# HB_UNIT.net
KiCad netlist of a schematic drawn in Altium Designer
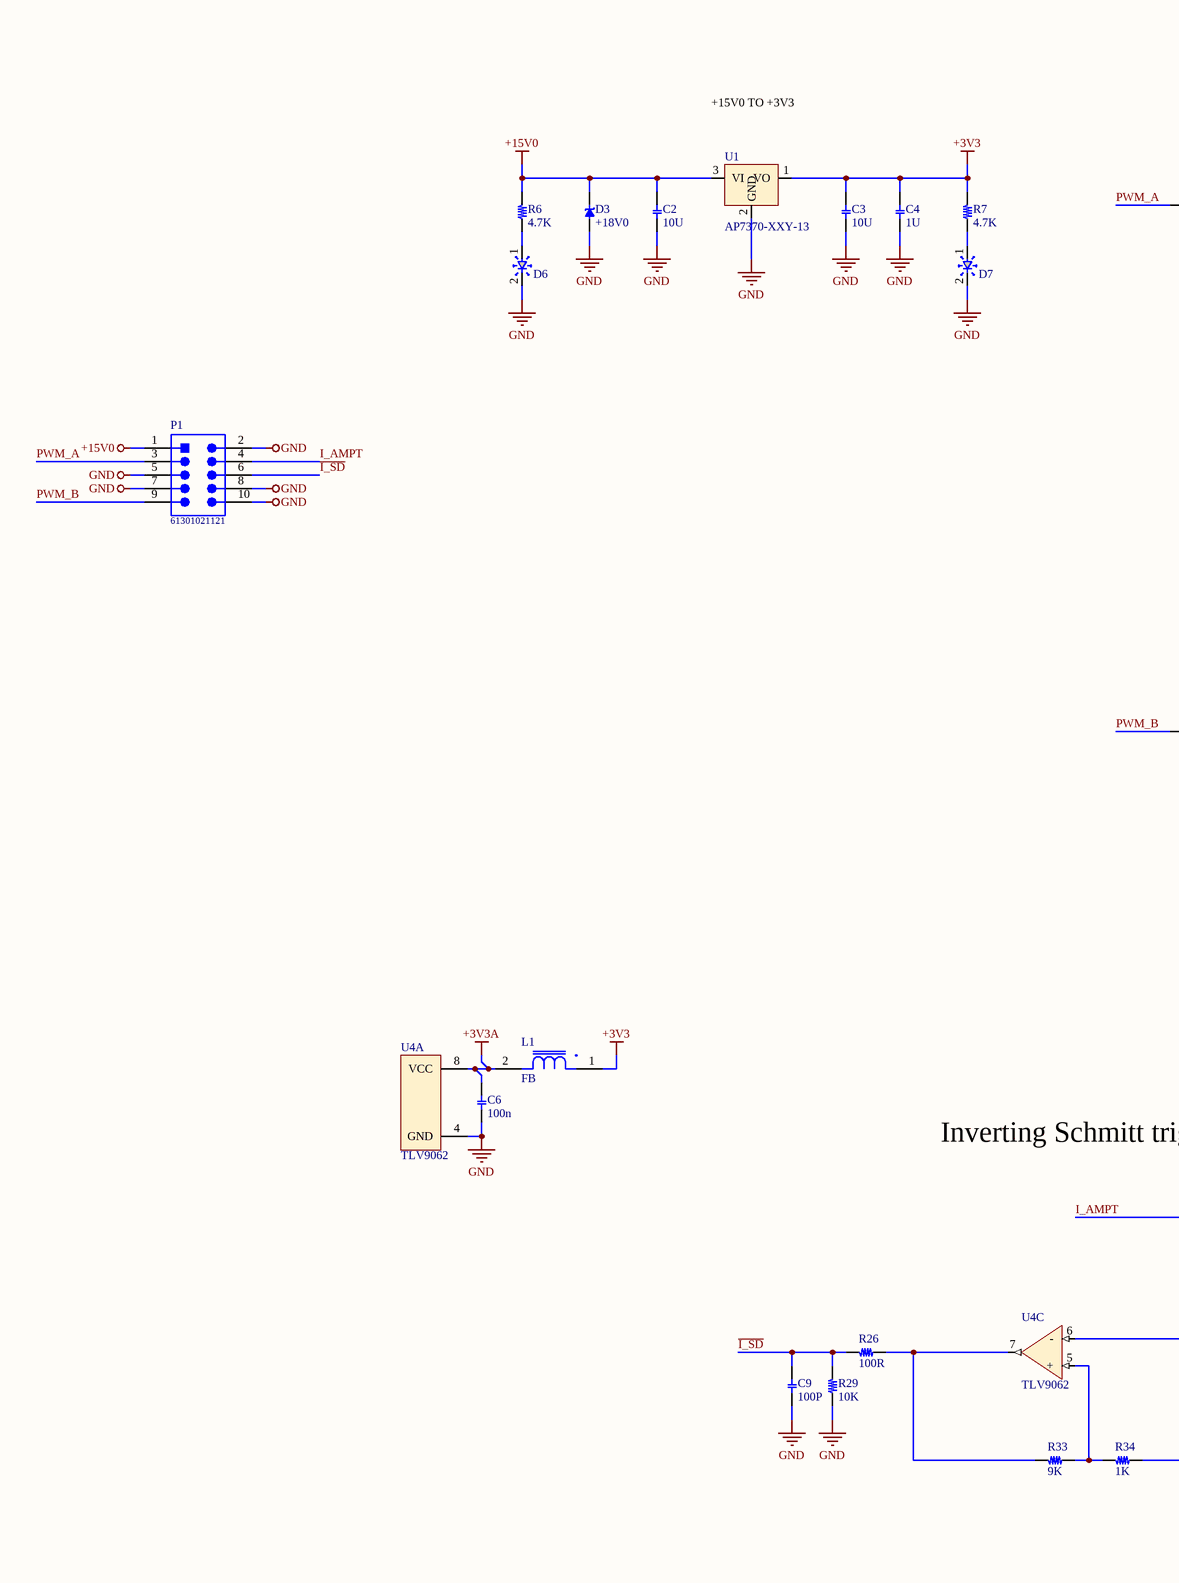
[diagram p0: HB_UNIT.SchDoc, left]
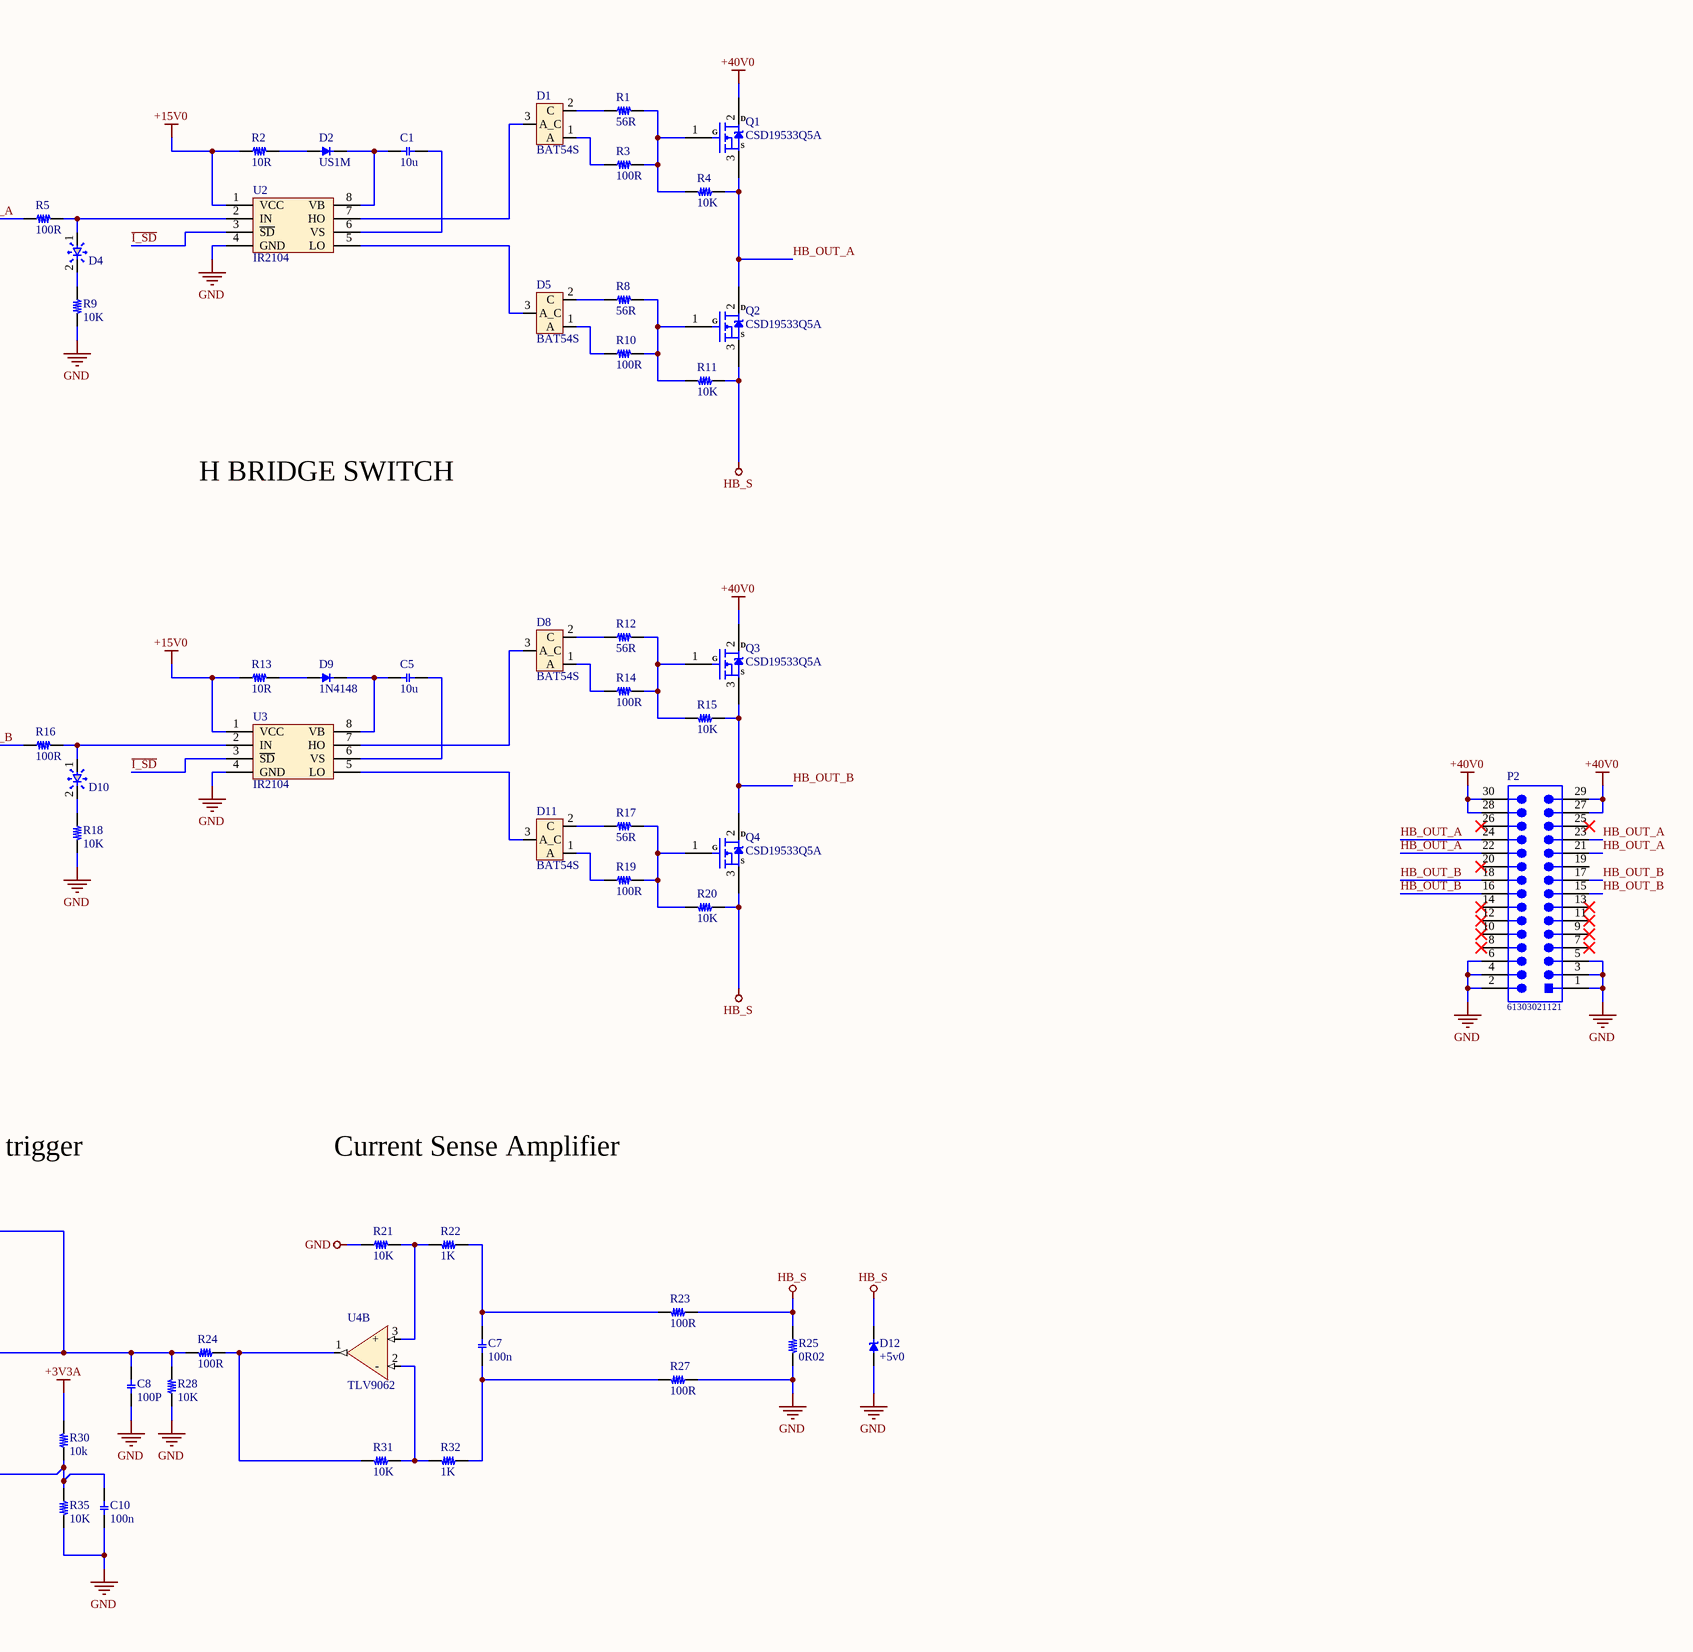
[diagram p1: HB_UNIT.SchDoc, right]

(export (version "E")
  (design (tool "Eeschema 10.0.6"))
  (components
    (comp (ref "C1")
      (value "10u")
      (footprint "C 0805")
      (description "CAP_SMD")
      (libsource (lib "radmehr_library") (part "CAP_SMD"))
    )
    (comp (ref "C2")
      (value "10U")
      (footprint "C 0603")
      (description "CAP_SMD")
      (libsource (lib "radmehr_library") (part "CAP_SMD"))
    )
    (comp (ref "C3")
      (value "10U")
      (footprint "C 0603")
      (description "CAP_SMD")
      (libsource (lib "radmehr_library") (part "CAP_SMD"))
    )
    (comp (ref "C4")
      (value "1U")
      (footprint "C 0603")
      (description "CAP_SMD")
      (libsource (lib "radmehr_library") (part "CAP_SMD"))
    )
    (comp (ref "C5")
      (value "10u")
      (footprint "C 0805")
      (description "CAP_SMD")
      (libsource (lib "radmehr_library") (part "CAP_SMD"))
    )
    (comp (ref "C6")
      (value "100n")
      (footprint "C 0603")
      (description "CAP_SMD")
      (libsource (lib "radmehr_library") (part "CAP_SMD"))
    )
    (comp (ref "C7")
      (value "100n")
      (footprint "C 0603")
      (description "CAP_SMD")
      (libsource (lib "radmehr_library") (part "CAP_SMD"))
    )
    (comp (ref "C8")
      (value "100P")
      (footprint "C 0603")
      (description "CAP_SMD")
      (libsource (lib "radmehr_library") (part "CAP_SMD"))
    )
    (comp (ref "C9")
      (value "100P")
      (footprint "C 0603")
      (description "CAP_SMD")
      (libsource (lib "radmehr_library") (part "CAP_SMD"))
    )
    (comp (ref "C10")
      (value "100n")
      (footprint "C 0603")
      (description "CAP_SMD")
      (libsource (lib "radmehr_library") (part "CAP_SMD"))
    )
    (comp (ref "D1")
      (value "BAT54S")
      (footprint "SOT-23_3_D")
      (libsource (lib "radmehr_library") (part "BAT54S"))
    )
    (comp (ref "D2")
      (value "US1M")
      (footprint "D SOD-123")
      (description "DIOD_SMD")
      (libsource (lib "radmehr_library") (part "DIOD_SMD"))
    )
    (comp (ref "D3")
      (value "+18V0")
      (footprint "DIOD_SMB")
      (description "TVS_UI")
      (libsource (lib "radmehr_library") (part "DIOD_SMD_TVS_UI"))
    )
    (comp (ref "D4")
      (value "LED_SMD")
      (footprint "D 0603")
      (libsource (lib "radmehr_library") (part "LED_SMD"))
    )
    (comp (ref "D5")
      (value "BAT54S")
      (footprint "SOT-23_3_D")
      (libsource (lib "radmehr_library") (part "BAT54S"))
    )
    (comp (ref "D6")
      (value "LED_SMD")
      (footprint "D 0603")
      (libsource (lib "radmehr_library") (part "LED_SMD"))
    )
    (comp (ref "D7")
      (value "LED_SMD")
      (footprint "D 0603")
      (libsource (lib "radmehr_library") (part "LED_SMD"))
    )
    (comp (ref "D8")
      (value "BAT54S")
      (footprint "SOT-23_3_D")
      (libsource (lib "radmehr_library") (part "BAT54S"))
    )
    (comp (ref "D9")
      (value "1N4148")
      (footprint "D SOD-123")
      (description "DIOD_SMD")
      (libsource (lib "radmehr_library") (part "DIOD_SMD"))
    )
    (comp (ref "D10")
      (value "LED_SMD")
      (footprint "D 0603")
      (libsource (lib "radmehr_library") (part "LED_SMD"))
    )
    (comp (ref "D11")
      (value "BAT54S")
      (footprint "SOT-23_3_D")
      (libsource (lib "radmehr_library") (part "BAT54S"))
    )
    (comp (ref "D12")
      (value "+5v0")
      (footprint "DIOD_SMB")
      (description "TVS_UI")
      (libsource (lib "radmehr_library") (part "DIOD_SMD_TVS_UI"))
    )
    (comp (ref "L1")
      (value "FB")
      (footprint "L 0603")
      (description "Inductor")
      (libsource (lib "radmehr_library") (part "Inductor"))
    )
    (comp (ref "P1")
      (value "61301021121")
      (footprint "61301021121")
      (description "WR-PHD Pin Header, THT, pitch 2.54mm, Dual Row, Vertical, 10p")
      (fields (field (name "MANUFACTURER") "Wurth Elektronik"))
      (libsource (lib "Altium_WR-PHD (rev22a)") (part "61301021121"))
    )
    (comp (ref "P2")
      (value "61303021121")
      (footprint "61303021121")
      (description "WR-PHD Pin Header, THT, pitch 2.54mm, Dual Row, Vertical, 30p")
      (fields (field (name "MANUFACTURER") "Wurth Elektronik"))
      (libsource (lib "Altium_WR-PHD (rev22a)") (part "61303021121"))
    )
    (comp (ref "Q1")
      (value "CSD19533Q5A")
      (footprint "Q5A")
      (libsource (lib "radmehr_library") (part "CSD19533Q5A"))
    )
    (comp (ref "Q2")
      (value "CSD19533Q5A")
      (footprint "Q5A")
      (libsource (lib "radmehr_library") (part "CSD19533Q5A"))
    )
    (comp (ref "Q3")
      (value "CSD19533Q5A")
      (footprint "Q5A")
      (libsource (lib "radmehr_library") (part "CSD19533Q5A"))
    )
    (comp (ref "Q4")
      (value "CSD19533Q5A")
      (footprint "Q5A")
      (libsource (lib "radmehr_library") (part "CSD19533Q5A"))
    )
    (comp (ref "R1")
      (value "56R")
      (footprint "R 0805")
      (description "RES_SMD")
      (libsource (lib "radmehr_library") (part "RES_SMD"))
    )
    (comp (ref "R2")
      (value "10R")
      (footprint "R 0805")
      (description "RES_SMD")
      (libsource (lib "radmehr_library") (part "RES_SMD"))
    )
    (comp (ref "R3")
      (value "100R")
      (footprint "R 0805")
      (description "RES_SMD")
      (libsource (lib "radmehr_library") (part "RES_SMD"))
    )
    (comp (ref "R4")
      (value "10K")
      (footprint "R 0603")
      (description "RES_SMD")
      (libsource (lib "radmehr_library") (part "RES_SMD"))
    )
    (comp (ref "R5")
      (value "100R")
      (footprint "R 0603")
      (description "RES_SMD")
      (libsource (lib "radmehr_library") (part "RES_SMD"))
    )
    (comp (ref "R6")
      (value "4.7K")
      (footprint "R 0603")
      (description "RES_SMD")
      (libsource (lib "radmehr_library") (part "RES_SMD"))
    )
    (comp (ref "R7")
      (value "4.7K")
      (footprint "R 0603")
      (description "RES_SMD")
      (libsource (lib "radmehr_library") (part "RES_SMD"))
    )
    (comp (ref "R8")
      (value "56R")
      (footprint "R 0805")
      (description "RES_SMD")
      (libsource (lib "radmehr_library") (part "RES_SMD"))
    )
    (comp (ref "R9")
      (value "10K")
      (footprint "R 0603")
      (description "RES_SMD")
      (libsource (lib "radmehr_library") (part "RES_SMD"))
    )
    (comp (ref "R10")
      (value "100R")
      (footprint "R 0805")
      (description "RES_SMD")
      (libsource (lib "radmehr_library") (part "RES_SMD"))
    )
    (comp (ref "R11")
      (value "10K")
      (footprint "R 0603")
      (description "RES_SMD")
      (libsource (lib "radmehr_library") (part "RES_SMD"))
    )
    (comp (ref "R12")
      (value "56R")
      (footprint "R 0805")
      (description "RES_SMD")
      (libsource (lib "radmehr_library") (part "RES_SMD"))
    )
    (comp (ref "R13")
      (value "10R")
      (footprint "R 0805")
      (description "RES_SMD")
      (libsource (lib "radmehr_library") (part "RES_SMD"))
    )
    (comp (ref "R14")
      (value "100R")
      (footprint "R 0805")
      (description "RES_SMD")
      (libsource (lib "radmehr_library") (part "RES_SMD"))
    )
    (comp (ref "R15")
      (value "10K")
      (footprint "R 0603")
      (description "RES_SMD")
      (libsource (lib "radmehr_library") (part "RES_SMD"))
    )
    (comp (ref "R16")
      (value "100R")
      (footprint "R 0603")
      (description "RES_SMD")
      (libsource (lib "radmehr_library") (part "RES_SMD"))
    )
    (comp (ref "R17")
      (value "56R")
      (footprint "R 0805")
      (description "RES_SMD")
      (libsource (lib "radmehr_library") (part "RES_SMD"))
    )
    (comp (ref "R18")
      (value "10K")
      (footprint "R 0603")
      (description "RES_SMD")
      (libsource (lib "radmehr_library") (part "RES_SMD"))
    )
    (comp (ref "R19")
      (value "100R")
      (footprint "R 0805")
      (description "RES_SMD")
      (libsource (lib "radmehr_library") (part "RES_SMD"))
    )
    (comp (ref "R20")
      (value "10K")
      (footprint "R 0603")
      (description "RES_SMD")
      (libsource (lib "radmehr_library") (part "RES_SMD"))
    )
    (comp (ref "R21")
      (value "10K")
      (footprint "R 0603")
      (description "RES_SMD")
      (libsource (lib "radmehr_library") (part "RES_SMD"))
    )
    (comp (ref "R22")
      (value "1K")
      (footprint "R 0603")
      (description "RES_SMD")
      (libsource (lib "radmehr_library") (part "RES_SMD"))
    )
    (comp (ref "R23")
      (value "100R")
      (footprint "R 0603")
      (description "RES_SMD")
      (libsource (lib "radmehr_library") (part "RES_SMD"))
    )
    (comp (ref "R24")
      (value "100R")
      (footprint "R 0603")
      (description "RES_SMD")
      (libsource (lib "radmehr_library") (part "RES_SMD"))
    )
    (comp (ref "R25")
      (value "0R02")
      (footprint "R 2512")
      (description "RES_SMD")
      (libsource (lib "radmehr_library") (part "RES_SMD"))
    )
    (comp (ref "R26")
      (value "100R")
      (footprint "R 0603")
      (description "RES_SMD")
      (libsource (lib "radmehr_library") (part "RES_SMD"))
    )
    (comp (ref "R27")
      (value "100R")
      (footprint "R 0603")
      (description "RES_SMD")
      (libsource (lib "radmehr_library") (part "RES_SMD"))
    )
    (comp (ref "R28")
      (value "10K")
      (footprint "R 0603")
      (description "RES_SMD")
      (libsource (lib "radmehr_library") (part "RES_SMD"))
    )
    (comp (ref "R29")
      (value "10K")
      (footprint "R 0603")
      (description "RES_SMD")
      (libsource (lib "radmehr_library") (part "RES_SMD"))
    )
    (comp (ref "R30")
      (value "10k")
      (footprint "R 0603")
      (description "RES_SMD")
      (libsource (lib "radmehr_library") (part "RES_SMD"))
    )
    (comp (ref "R31")
      (value "10K")
      (footprint "R 0603")
      (description "RES_SMD")
      (libsource (lib "radmehr_library") (part "RES_SMD"))
    )
    (comp (ref "R32")
      (value "1K")
      (footprint "R 0603")
      (description "RES_SMD")
      (libsource (lib "radmehr_library") (part "RES_SMD"))
    )
    (comp (ref "R33")
      (value "9K")
      (footprint "R 0603")
      (description "RES_SMD")
      (libsource (lib "radmehr_library") (part "RES_SMD"))
    )
    (comp (ref "R34")
      (value "1K")
      (footprint "R 0603")
      (description "RES_SMD")
      (libsource (lib "radmehr_library") (part "RES_SMD"))
    )
    (comp (ref "R35")
      (value "10K")
      (footprint "R 0603")
      (description "RES_SMD")
      (libsource (lib "radmehr_library") (part "RES_SMD"))
    )
    (comp (ref "U1")
      (value "AP7370-XXY-13")
      (footprint "SOT89-U")
      (libsource (lib "radmehr_library") (part "AP7370-XXY-13"))
    )
    (comp (ref "U2")
      (value "IR2104")
      (footprint "SOIC-8")
      (libsource (lib "radmehr_library") (part "IR2104"))
    )
    (comp (ref "U3")
      (value "IR2104")
      (footprint "SOIC-8")
      (libsource (lib "radmehr_library") (part "IR2104"))
    )
    (comp (ref "U4")
      (value "TLV9062")
      (footprint "SOIC-8")
      (libsource (lib "radmehr_library") (part "TLV9062"))
    )
  )
  (nets
    (net (code "1") (name "+3V3") (class "Default")
      (node (ref "C3") (pin "2") (pinfunction "2_2") (pintype "passive"))
      (node (ref "C4") (pin "2") (pinfunction "2_2") (pintype "passive"))
      (node (ref "L1") (pin "1") (pintype "passive"))
      (node (ref "R7") (pin "2") (pinfunction "2_2") (pintype "passive"))
      (node (ref "U1") (pin "1") (pinfunction "VO_1") (pintype "passive"))
    )
    (net (code "2") (name "+3V3A") (class "Default")
      (node (ref "C6") (pin "2") (pinfunction "2_2") (pintype "passive"))
      (node (ref "L1") (pin "2") (pintype "passive"))
      (node (ref "R30") (pin "1") (pinfunction "1_1") (pintype "passive"))
      (node (ref "U4") (pin "8") (pinfunction "VCC_8") (pintype "passive"))
    )
    (net (code "3") (name "+15V0") (class "Default")
      (node (ref "C2") (pin "2") (pinfunction "2_2") (pintype "passive"))
      (node (ref "D3") (pin "2") (pinfunction "2_2") (pintype "passive"))
      (node (ref "P1") (pin "1") (pinfunction "1_1") (pintype "passive"))
      (node (ref "R13") (pin "1") (pinfunction "1_1") (pintype "passive"))
      (node (ref "R2") (pin "1") (pinfunction "1_1") (pintype "passive"))
      (node (ref "R6") (pin "2") (pinfunction "2_2") (pintype "passive"))
      (node (ref "U1") (pin "3") (pinfunction "VI_3") (pintype "passive"))
      (node (ref "U2") (pin "1") (pinfunction "VCC_1") (pintype "passive"))
      (node (ref "U3") (pin "1") (pinfunction "VCC_1") (pintype "passive"))
    )
    (net (code "4") (name "+40V0") (class "Default")
      (node (ref "P2") (pin "27") (pinfunction "27_27") (pintype "passive"))
      (node (ref "P2") (pin "28") (pinfunction "28_28") (pintype "passive"))
      (node (ref "P2") (pin "29") (pinfunction "29_29") (pintype "passive"))
      (node (ref "P2") (pin "30") (pinfunction "30_30") (pintype "passive"))
      (node (ref "Q1") (pin "2") (pinfunction "D_2") (pintype "passive"))
      (node (ref "Q3") (pin "2") (pinfunction "D_2") (pintype "passive"))
    )
    (net (code "5") (name "/HB_OUT_A") (class "Default")
      (node (ref "P2") (pin "21") (pinfunction "21_21") (pintype "passive"))
      (node (ref "P2") (pin "22") (pinfunction "22_22") (pintype "passive"))
      (node (ref "P2") (pin "23") (pinfunction "23_23") (pintype "passive"))
      (node (ref "P2") (pin "24") (pinfunction "24_24") (pintype "passive"))
      (node (ref "Q1") (pin "3") (pinfunction "S_3") (pintype "passive"))
      (node (ref "Q2") (pin "2") (pinfunction "D_2") (pintype "passive"))
      (node (ref "R4") (pin "1") (pinfunction "1_1") (pintype "passive"))
    )
    (net (code "6") (name "/HB_OUT_B") (class "Default")
      (node (ref "P2") (pin "15") (pinfunction "15_15") (pintype "passive"))
      (node (ref "P2") (pin "16") (pinfunction "16_16") (pintype "passive"))
      (node (ref "P2") (pin "17") (pinfunction "17_17") (pintype "passive"))
      (node (ref "P2") (pin "18") (pinfunction "18_18") (pintype "passive"))
      (node (ref "Q3") (pin "3") (pinfunction "S_3") (pintype "passive"))
      (node (ref "Q4") (pin "2") (pinfunction "D_2") (pintype "passive"))
      (node (ref "R15") (pin "1") (pinfunction "1_1") (pintype "passive"))
    )
    (net (code "7") (name "/I_AMPT") (class "Default")
      (node (ref "C8") (pin "2") (pinfunction "2_2") (pintype "passive"))
      (node (ref "P1") (pin "4") (pinfunction "4_4") (pintype "passive"))
      (node (ref "R24") (pin "2") (pinfunction "2_2") (pintype "passive"))
      (node (ref "R28") (pin "2") (pinfunction "2_2") (pintype "passive"))
      (node (ref "U4") (pin "6") (pinfunction "-_6") (pintype "input"))
    )
    (net (code "8") (name "/PWM_A") (class "Default")
      (node (ref "P1") (pin "3") (pinfunction "3_3") (pintype "passive"))
      (node (ref "R5") (pin "1") (pinfunction "1_1") (pintype "passive"))
    )
    (net (code "9") (name "/PWM_B") (class "Default")
      (node (ref "P1") (pin "9") (pinfunction "9_9") (pintype "passive"))
      (node (ref "R16") (pin "1") (pinfunction "1_1") (pintype "passive"))
    )
    (net (code "10") (name "/~{I_SD}") (class "Default")
      (node (ref "C9") (pin "2") (pinfunction "2_2") (pintype "passive"))
      (node (ref "P1") (pin "6") (pinfunction "6_6") (pintype "passive"))
      (node (ref "R26") (pin "2") (pinfunction "2_2") (pintype "passive"))
      (node (ref "R29") (pin "2") (pinfunction "2_2") (pintype "passive"))
      (node (ref "U2") (pin "3") (pinfunction "~{SD}_3") (pintype "passive"))
      (node (ref "U3") (pin "3") (pinfunction "~{SD}_3") (pintype "passive"))
    )
    (net (code "11") (name "GND") (class "Default")
      (node (ref "C10") (pin "2") (pinfunction "2_2") (pintype "passive"))
      (node (ref "C2") (pin "1") (pinfunction "1_1") (pintype "passive"))
      (node (ref "C3") (pin "1") (pinfunction "1_1") (pintype "passive"))
      (node (ref "C4") (pin "1") (pinfunction "1_1") (pintype "passive"))
      (node (ref "C6") (pin "1") (pinfunction "1_1") (pintype "passive"))
      (node (ref "C8") (pin "1") (pinfunction "1_1") (pintype "passive"))
      (node (ref "C9") (pin "1") (pinfunction "1_1") (pintype "passive"))
      (node (ref "D12") (pin "1") (pinfunction "1_1") (pintype "passive"))
      (node (ref "D3") (pin "1") (pinfunction "1_1") (pintype "passive"))
      (node (ref "D6") (pin "2") (pintype "passive"))
      (node (ref "D7") (pin "2") (pintype "passive"))
      (node (ref "P1") (pin "10") (pinfunction "10_10") (pintype "passive"))
      (node (ref "P1") (pin "2") (pinfunction "2_2") (pintype "passive"))
      (node (ref "P1") (pin "5") (pinfunction "5_5") (pintype "passive"))
      (node (ref "P1") (pin "7") (pinfunction "7_7") (pintype "passive"))
      (node (ref "P1") (pin "8") (pinfunction "8_8") (pintype "passive"))
      (node (ref "P2") (pin "1") (pinfunction "1_1") (pintype "passive"))
      (node (ref "P2") (pin "2") (pinfunction "2_2") (pintype "passive"))
      (node (ref "P2") (pin "3") (pinfunction "3_3") (pintype "passive"))
      (node (ref "P2") (pin "4") (pinfunction "4_4") (pintype "passive"))
      (node (ref "P2") (pin "5") (pinfunction "5_5") (pintype "passive"))
      (node (ref "P2") (pin "6") (pinfunction "6_6") (pintype "passive"))
      (node (ref "R18") (pin "1") (pinfunction "1_1") (pintype "passive"))
      (node (ref "R21") (pin "1") (pinfunction "1_1") (pintype "passive"))
      (node (ref "R25") (pin "1") (pinfunction "1_1") (pintype "passive"))
      (node (ref "R27") (pin "1") (pinfunction "1_1") (pintype "passive"))
      (node (ref "R28") (pin "1") (pinfunction "1_1") (pintype "passive"))
      (node (ref "R29") (pin "1") (pinfunction "1_1") (pintype "passive"))
      (node (ref "R35") (pin "1") (pinfunction "1_1") (pintype "passive"))
      (node (ref "R9") (pin "1") (pinfunction "1_1") (pintype "passive"))
      (node (ref "U1") (pin "2") (pinfunction "GND_2") (pintype "passive"))
      (node (ref "U2") (pin "4") (pinfunction "GND_4") (pintype "passive"))
      (node (ref "U3") (pin "4") (pinfunction "GND_4") (pintype "passive"))
      (node (ref "U4") (pin "4") (pinfunction "GND_4") (pintype "passive"))
    )
    (net (code "12") (name "HB_S") (class "Default")
      (node (ref "D12") (pin "2") (pinfunction "2_2") (pintype "passive"))
      (node (ref "Q2") (pin "3") (pinfunction "S_3") (pintype "passive"))
      (node (ref "Q4") (pin "3") (pinfunction "S_3") (pintype "passive"))
      (node (ref "R11") (pin "1") (pinfunction "1_1") (pintype "passive"))
      (node (ref "R20") (pin "1") (pinfunction "1_1") (pintype "passive"))
      (node (ref "R23") (pin "1") (pinfunction "1_1") (pintype "passive"))
      (node (ref "R25") (pin "2") (pinfunction "2_2") (pintype "passive"))
    )
    (net (code "13") (name "Net-(C7-Pad1)") (class "Default")
      (node (ref "C7") (pin "1") (pinfunction "1_1") (pintype "passive"))
      (node (ref "R27") (pin "2") (pinfunction "2_2") (pintype "passive"))
      (node (ref "R32") (pin "1") (pinfunction "1_1") (pintype "passive"))
    )
    (net (code "14") (name "Net-(C7-Pad2)") (class "Default")
      (node (ref "C7") (pin "2") (pinfunction "2_2") (pintype "passive"))
      (node (ref "R22") (pin "1") (pinfunction "1_1") (pintype "passive"))
      (node (ref "R23") (pin "2") (pinfunction "2_2") (pintype "passive"))
    )
    (net (code "15") (name "Net-(C10-Pad1)") (class "Default")
      (node (ref "C10") (pin "1") (pinfunction "1_1") (pintype "passive"))
      (node (ref "R30") (pin "2") (pinfunction "2_2") (pintype "passive"))
      (node (ref "R34") (pin "1") (pinfunction "1_1") (pintype "passive"))
      (node (ref "R35") (pin "2") (pinfunction "2_2") (pintype "passive"))
    )
    (net (code "16") (name "Net-(D1-A)") (class "Default")
      (node (ref "D1") (pin "1") (pinfunction "A_1") (pintype "passive"))
      (node (ref "R3") (pin "1") (pinfunction "1_1") (pintype "passive"))
    )
    (net (code "17") (name "Net-(D1-A_C)") (class "Default")
      (node (ref "D1") (pin "3") (pinfunction "A_C_3") (pintype "passive"))
      (node (ref "U2") (pin "7") (pinfunction "HO_7") (pintype "passive"))
    )
    (net (code "18") (name "Net-(D1-C)") (class "Default")
      (node (ref "D1") (pin "2") (pinfunction "C_2") (pintype "passive"))
      (node (ref "R1") (pin "1") (pinfunction "1_1") (pintype "passive"))
    )
    (net (code "19") (name "Net-(D2-Pad1)") (class "Default")
      (node (ref "D2") (pin "1") (pinfunction "1_1") (pintype "passive"))
      (node (ref "R2") (pin "2") (pinfunction "2_2") (pintype "passive"))
    )
    (net (code "20") (name "Net-(D4-Pad2)") (class "Default")
      (node (ref "D4") (pin "2") (pintype "passive"))
      (node (ref "R9") (pin "2") (pinfunction "2_2") (pintype "passive"))
    )
    (net (code "21") (name "Net-(D5-A)") (class "Default")
      (node (ref "D5") (pin "1") (pinfunction "A_1") (pintype "passive"))
      (node (ref "R10") (pin "1") (pinfunction "1_1") (pintype "passive"))
    )
    (net (code "22") (name "Net-(D5-A_C)") (class "Default")
      (node (ref "D5") (pin "3") (pinfunction "A_C_3") (pintype "passive"))
      (node (ref "U2") (pin "5") (pinfunction "LO_5") (pintype "passive"))
    )
    (net (code "23") (name "Net-(D5-C)") (class "Default")
      (node (ref "D5") (pin "2") (pinfunction "C_2") (pintype "passive"))
      (node (ref "R8") (pin "1") (pinfunction "1_1") (pintype "passive"))
    )
    (net (code "24") (name "Net-(D6-Pad1)") (class "Default")
      (node (ref "D6") (pin "1") (pintype "passive"))
      (node (ref "R6") (pin "1") (pinfunction "1_1") (pintype "passive"))
    )
    (net (code "25") (name "Net-(D7-Pad1)") (class "Default")
      (node (ref "D7") (pin "1") (pintype "passive"))
      (node (ref "R7") (pin "1") (pinfunction "1_1") (pintype "passive"))
    )
    (net (code "26") (name "Net-(D8-A)") (class "Default")
      (node (ref "D8") (pin "1") (pinfunction "A_1") (pintype "passive"))
      (node (ref "R14") (pin "1") (pinfunction "1_1") (pintype "passive"))
    )
    (net (code "27") (name "Net-(D8-A_C)") (class "Default")
      (node (ref "D8") (pin "3") (pinfunction "A_C_3") (pintype "passive"))
      (node (ref "U3") (pin "7") (pinfunction "HO_7") (pintype "passive"))
    )
    (net (code "28") (name "Net-(D8-C)") (class "Default")
      (node (ref "D8") (pin "2") (pinfunction "C_2") (pintype "passive"))
      (node (ref "R12") (pin "1") (pinfunction "1_1") (pintype "passive"))
    )
    (net (code "29") (name "Net-(D9-Pad1)") (class "Default")
      (node (ref "D9") (pin "1") (pinfunction "1_1") (pintype "passive"))
      (node (ref "R13") (pin "2") (pinfunction "2_2") (pintype "passive"))
    )
    (net (code "30") (name "Net-(D10-Pad2)") (class "Default")
      (node (ref "D10") (pin "2") (pintype "passive"))
      (node (ref "R18") (pin "2") (pinfunction "2_2") (pintype "passive"))
    )
    (net (code "31") (name "Net-(D11-A)") (class "Default")
      (node (ref "D11") (pin "1") (pinfunction "A_1") (pintype "passive"))
      (node (ref "R19") (pin "1") (pinfunction "1_1") (pintype "passive"))
    )
    (net (code "32") (name "Net-(D11-A_C)") (class "Default")
      (node (ref "D11") (pin "3") (pinfunction "A_C_3") (pintype "passive"))
      (node (ref "U3") (pin "5") (pinfunction "LO_5") (pintype "passive"))
    )
    (net (code "33") (name "Net-(D11-C)") (class "Default")
      (node (ref "D11") (pin "2") (pinfunction "C_2") (pintype "passive"))
      (node (ref "R17") (pin "1") (pinfunction "1_1") (pintype "passive"))
    )
    (net (code "34") (name "Net-(Q1-G)") (class "Default")
      (node (ref "Q1") (pin "1") (pinfunction "G_1") (pintype "passive"))
      (node (ref "R1") (pin "2") (pinfunction "2_2") (pintype "passive"))
      (node (ref "R3") (pin "2") (pinfunction "2_2") (pintype "passive"))
      (node (ref "R4") (pin "2") (pinfunction "2_2") (pintype "passive"))
    )
    (net (code "35") (name "Net-(Q2-G)") (class "Default")
      (node (ref "Q2") (pin "1") (pinfunction "G_1") (pintype "passive"))
      (node (ref "R10") (pin "2") (pinfunction "2_2") (pintype "passive"))
      (node (ref "R11") (pin "2") (pinfunction "2_2") (pintype "passive"))
      (node (ref "R8") (pin "2") (pinfunction "2_2") (pintype "passive"))
    )
    (net (code "36") (name "Net-(Q3-G)") (class "Default")
      (node (ref "Q3") (pin "1") (pinfunction "G_1") (pintype "passive"))
      (node (ref "R12") (pin "2") (pinfunction "2_2") (pintype "passive"))
      (node (ref "R14") (pin "2") (pinfunction "2_2") (pintype "passive"))
      (node (ref "R15") (pin "2") (pinfunction "2_2") (pintype "passive"))
    )
    (net (code "37") (name "Net-(Q4-G)") (class "Default")
      (node (ref "Q4") (pin "1") (pinfunction "G_1") (pintype "passive"))
      (node (ref "R17") (pin "2") (pinfunction "2_2") (pintype "passive"))
      (node (ref "R19") (pin "2") (pinfunction "2_2") (pintype "passive"))
      (node (ref "R20") (pin "2") (pinfunction "2_2") (pintype "passive"))
    )
    (net (code "38") (name "Net-(U2-IN)") (class "Default")
      (node (ref "D4") (pin "1") (pintype "passive"))
      (node (ref "R5") (pin "2") (pinfunction "2_2") (pintype "passive"))
      (node (ref "U2") (pin "2") (pinfunction "IN_2") (pintype "passive"))
    )
    (net (code "39") (name "Net-(U2-VB)") (class "Default")
      (node (ref "C1") (pin "1") (pinfunction "1_1") (pintype "passive"))
      (node (ref "D2") (pin "2") (pinfunction "2_2") (pintype "passive"))
      (node (ref "U2") (pin "8") (pinfunction "VB_8") (pintype "passive"))
    )
    (net (code "40") (name "Net-(U2-VS)") (class "Default")
      (node (ref "C1") (pin "2") (pinfunction "2_2") (pintype "passive"))
      (node (ref "U2") (pin "6") (pinfunction "VS_6") (pintype "passive"))
    )
    (net (code "41") (name "Net-(U3-IN)") (class "Default")
      (node (ref "D10") (pin "1") (pintype "passive"))
      (node (ref "R16") (pin "2") (pinfunction "2_2") (pintype "passive"))
      (node (ref "U3") (pin "2") (pinfunction "IN_2") (pintype "passive"))
    )
    (net (code "42") (name "Net-(U3-VB)") (class "Default")
      (node (ref "C5") (pin "1") (pinfunction "1_1") (pintype "passive"))
      (node (ref "D9") (pin "2") (pinfunction "2_2") (pintype "passive"))
      (node (ref "U3") (pin "8") (pinfunction "VB_8") (pintype "passive"))
    )
    (net (code "43") (name "Net-(U3-VS)") (class "Default")
      (node (ref "C5") (pin "2") (pinfunction "2_2") (pintype "passive"))
      (node (ref "U3") (pin "6") (pinfunction "VS_6") (pintype "passive"))
    )
    (net (code "44") (name "Net-(U4B-+)") (class "Default")
      (node (ref "R21") (pin "2") (pinfunction "2_2") (pintype "passive"))
      (node (ref "R22") (pin "2") (pinfunction "2_2") (pintype "passive"))
      (node (ref "U4") (pin "3") (pinfunction "+_3") (pintype "input"))
    )
    (net (code "45") (name "Net-(U4B--)") (class "Default")
      (node (ref "R31") (pin "1") (pinfunction "1_1") (pintype "passive"))
      (node (ref "R32") (pin "2") (pinfunction "2_2") (pintype "passive"))
      (node (ref "U4") (pin "2") (pinfunction "-_2") (pintype "input"))
    )
    (net (code "46") (name "Net-(U4B-OUT)") (class "Default")
      (node (ref "R24") (pin "1") (pinfunction "1_1") (pintype "passive"))
      (node (ref "R31") (pin "2") (pinfunction "2_2") (pintype "passive"))
      (node (ref "U4") (pin "1") (pinfunction "OUT_1") (pintype "output"))
    )
    (net (code "47") (name "Net-(U4C-+)") (class "Default")
      (node (ref "R33") (pin "1") (pinfunction "1_1") (pintype "passive"))
      (node (ref "R34") (pin "2") (pinfunction "2_2") (pintype "passive"))
      (node (ref "U4") (pin "5") (pinfunction "+_5") (pintype "input"))
    )
    (net (code "48") (name "Net-(U4C-OUT)") (class "Default")
      (node (ref "R26") (pin "1") (pinfunction "1_1") (pintype "passive"))
      (node (ref "R33") (pin "2") (pinfunction "2_2") (pintype "passive"))
      (node (ref "U4") (pin "7") (pinfunction "OUT_7") (pintype "output"))
    )
    (net (code "49") (name "unconnected-(P2-Pad7)") (class "Default")
      (node (ref "P2") (pin "7") (pinfunction "7_7") (pintype "passive+no_connect"))
    )
    (net (code "50") (name "unconnected-(P2-Pad8)") (class "Default")
      (node (ref "P2") (pin "8") (pinfunction "8_8") (pintype "passive+no_connect"))
    )
    (net (code "51") (name "unconnected-(P2-Pad9)") (class "Default")
      (node (ref "P2") (pin "9") (pinfunction "9_9") (pintype "passive+no_connect"))
    )
    (net (code "52") (name "unconnected-(P2-Pad10)") (class "Default")
      (node (ref "P2") (pin "10") (pinfunction "10_10") (pintype "passive+no_connect"))
    )
    (net (code "53") (name "unconnected-(P2-Pad11)") (class "Default")
      (node (ref "P2") (pin "11") (pinfunction "11_11") (pintype "passive+no_connect"))
    )
    (net (code "54") (name "unconnected-(P2-Pad12)") (class "Default")
      (node (ref "P2") (pin "12") (pinfunction "12_12") (pintype "passive+no_connect"))
    )
    (net (code "55") (name "unconnected-(P2-Pad13)") (class "Default")
      (node (ref "P2") (pin "13") (pinfunction "13_13") (pintype "passive+no_connect"))
    )
    (net (code "56") (name "unconnected-(P2-Pad14)") (class "Default")
      (node (ref "P2") (pin "14") (pinfunction "14_14") (pintype "passive+no_connect"))
    )
    (net (code "57") (name "unconnected-(P2-Pad19)") (class "Default")
      (node (ref "P2") (pin "19") (pinfunction "19_19") (pintype "passive"))
    )
    (net (code "58") (name "unconnected-(P2-Pad20)") (class "Default")
      (node (ref "P2") (pin "20") (pinfunction "20_20") (pintype "passive+no_connect"))
    )
    (net (code "59") (name "unconnected-(P2-Pad25)") (class "Default")
      (node (ref "P2") (pin "25") (pinfunction "25_25") (pintype "passive+no_connect"))
    )
    (net (code "60") (name "unconnected-(P2-Pad26)") (class "Default")
      (node (ref "P2") (pin "26") (pinfunction "26_26") (pintype "passive+no_connect"))
    )
  )
)
